# anemo5.net
KiCad netlist of a schematic drawn in EAGLE
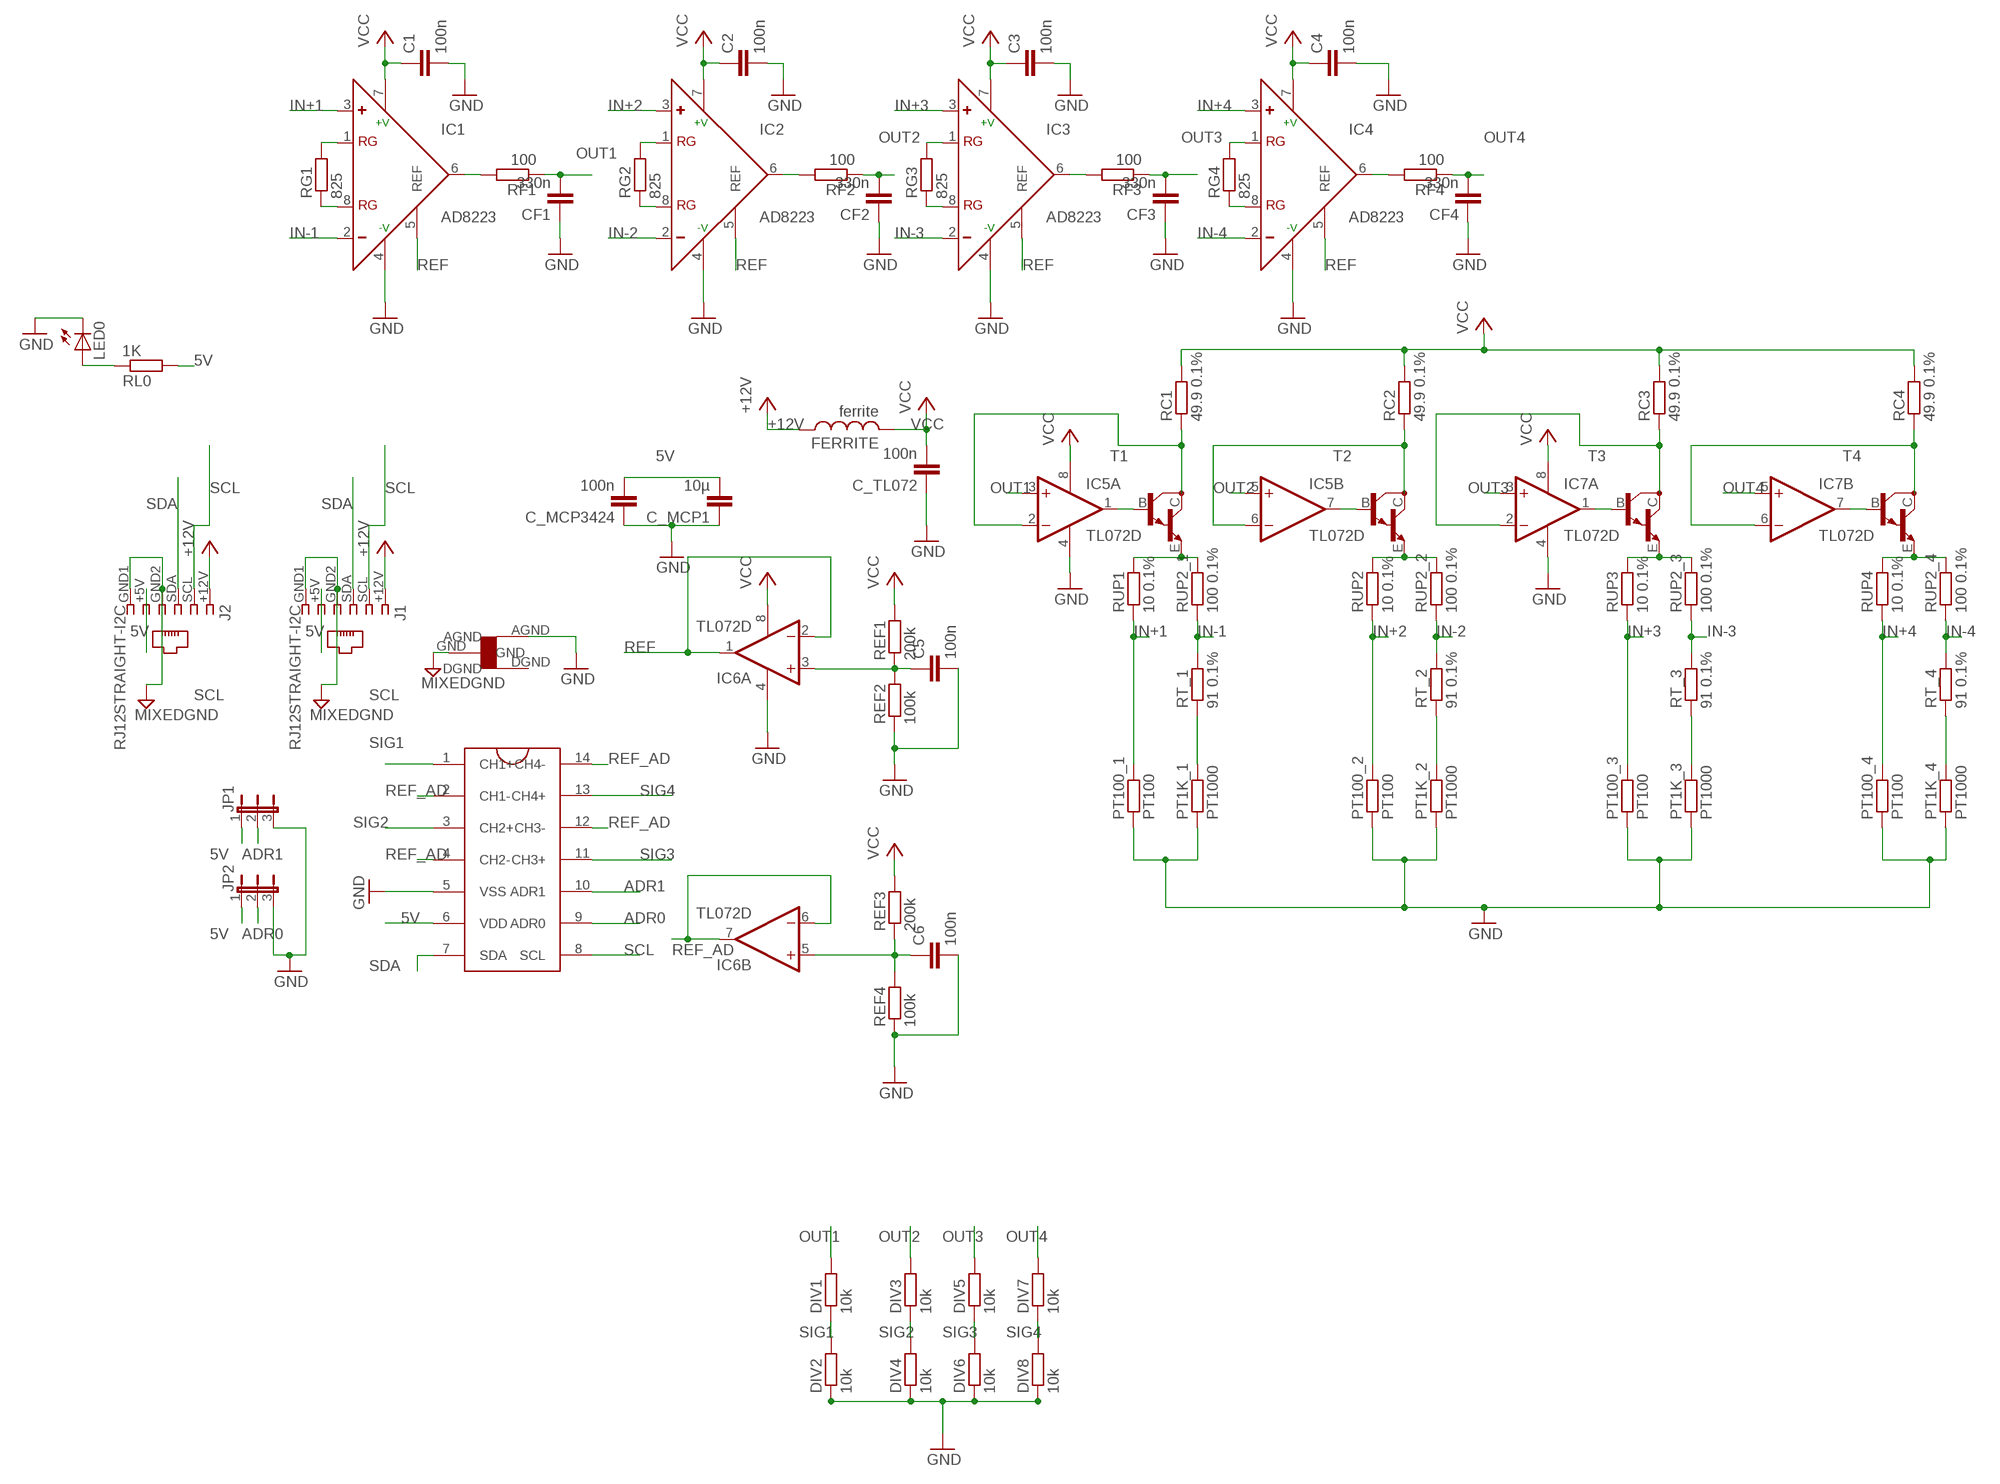
[diagram p0: schematic, sheet 1]

(export (version "E")
  (design (tool "Eeschema 10.0.6"))
  (components
    (comp (ref "C1")
      (value "100n")
      (footprint "eagle-import:C1206")
      (libsource (lib "eagle-import") (part "C-EUC1206"))
    )
    (comp (ref "C2")
      (value "100n")
      (footprint "eagle-import:C1206")
      (libsource (lib "eagle-import") (part "C-EUC1206"))
    )
    (comp (ref "C3")
      (value "100n")
      (footprint "eagle-import:C1206")
      (libsource (lib "eagle-import") (part "C-EUC1206"))
    )
    (comp (ref "C4")
      (value "100n")
      (footprint "eagle-import:C1206")
      (libsource (lib "eagle-import") (part "C-EUC1206"))
    )
    (comp (ref "C5")
      (value "100n")
      (footprint "eagle-import:C1206")
      (libsource (lib "eagle-import") (part "C-EUC1206"))
    )
    (comp (ref "C6")
      (value "100n")
      (footprint "eagle-import:C1206")
      (libsource (lib "eagle-import") (part "C-EUC1206"))
    )
    (comp (ref "CF1")
      (value "330n")
      (footprint "eagle-import:C1206")
      (libsource (lib "eagle-import") (part "C-EUC1206"))
    )
    (comp (ref "CF2")
      (value "330n")
      (footprint "eagle-import:C1206")
      (libsource (lib "eagle-import") (part "C-EUC1206"))
    )
    (comp (ref "CF3")
      (value "330n")
      (footprint "eagle-import:C1206")
      (libsource (lib "eagle-import") (part "C-EUC1206"))
    )
    (comp (ref "CF4")
      (value "330n")
      (footprint "eagle-import:C1206")
      (libsource (lib "eagle-import") (part "C-EUC1206"))
    )
    (comp (ref "C_MCP1")
      (value "10µ")
      (footprint "eagle-import:C1206")
      (libsource (lib "eagle-import") (part "C-EUC1206"))
    )
    (comp (ref "C_MCP3424")
      (value "100n")
      (footprint "eagle-import:C1206")
      (libsource (lib "eagle-import") (part "C-EUC1206"))
    )
    (comp (ref "C_TL072")
      (value "100n")
      (footprint "eagle-import:C1206")
      (libsource (lib "eagle-import") (part "C-EUC1206"))
    )
    (comp (ref "DIV1")
      (value "10k")
      (footprint "eagle-import:M1206")
      (libsource (lib "eagle-import") (part "R-EU_M1206"))
    )
    (comp (ref "DIV2")
      (value "10k")
      (footprint "eagle-import:M1206")
      (libsource (lib "eagle-import") (part "R-EU_M1206"))
    )
    (comp (ref "DIV3")
      (value "10k")
      (footprint "eagle-import:M1206")
      (libsource (lib "eagle-import") (part "R-EU_M1206"))
    )
    (comp (ref "DIV4")
      (value "10k")
      (footprint "eagle-import:M1206")
      (libsource (lib "eagle-import") (part "R-EU_M1206"))
    )
    (comp (ref "DIV5")
      (value "10k")
      (footprint "eagle-import:M1206")
      (libsource (lib "eagle-import") (part "R-EU_M1206"))
    )
    (comp (ref "DIV6")
      (value "10k")
      (footprint "eagle-import:M1206")
      (libsource (lib "eagle-import") (part "R-EU_M1206"))
    )
    (comp (ref "DIV7")
      (value "10k")
      (footprint "eagle-import:M1206")
      (libsource (lib "eagle-import") (part "R-EU_M1206"))
    )
    (comp (ref "DIV8")
      (value "10k")
      (footprint "eagle-import:M1206")
      (libsource (lib "eagle-import") (part "R-EU_M1206"))
    )
    (comp (ref "FERRITE")
      (value "ferrite")
      (footprint "eagle-import:L3216C")
      (libsource (lib "eagle-import") (part "L-USL3216C"))
    )
    (comp (ref "IC1")
      (value "AD8223")
      (footprint "eagle-import:SO8")
      (fields (field (name "MPN") "AD620AR"))
      (libsource (lib "eagle-import") (part "AD620R"))
    )
    (comp (ref "IC2")
      (value "AD8223")
      (footprint "eagle-import:SO8")
      (fields (field (name "MPN") "AD620AR"))
      (libsource (lib "eagle-import") (part "AD620R"))
    )
    (comp (ref "IC3")
      (value "AD8223")
      (footprint "eagle-import:SO8")
      (fields (field (name "MPN") "AD620AR"))
      (libsource (lib "eagle-import") (part "AD620R"))
    )
    (comp (ref "IC4")
      (value "AD8223")
      (footprint "eagle-import:SO8")
      (fields (field (name "MPN") "AD620AR"))
      (libsource (lib "eagle-import") (part "AD620R"))
    )
    (comp (ref "IC5")
      (value "TL072D")
      (footprint "eagle-import:SO08")
      (libsource (lib "eagle-import") (part "TL072D"))
    )
    (comp (ref "IC6")
      (value "TL072D")
      (footprint "eagle-import:SO08")
      (libsource (lib "eagle-import") (part "TL072D"))
    )
    (comp (ref "IC7")
      (value "TL072D")
      (footprint "eagle-import:SO08")
      (libsource (lib "eagle-import") (part "TL072D"))
    )
    (comp (ref "J1")
      (value "RJ12STRAIGHT-I2C")
      (footprint "eagle-import:RJ12-STRAIGHT-I2C")
      (libsource (lib "eagle-import") (part "RJ12STRAIGHT-I2C"))
    )
    (comp (ref "J2")
      (value "RJ12STRAIGHT-I2C")
      (footprint "eagle-import:RJ12-STRAIGHT-I2C")
      (libsource (lib "eagle-import") (part "RJ12STRAIGHT-I2C"))
    )
    (comp (ref "JP1")
      (value "JP2E")
      (footprint "eagle-import:JP2")
      (libsource (lib "eagle-import") (part "JP2E"))
    )
    (comp (ref "JP2")
      (value "JP2E")
      (footprint "eagle-import:JP2")
      (libsource (lib "eagle-import") (part "JP2E"))
    )
    (comp (ref "LED0")
      (value "LED1206")
      (footprint "eagle-import:LED-1206")
      (libsource (lib "eagle-import") (part "LED1206"))
    )
    (comp (ref "PT1K_1")
      (value "PT1000")
      (footprint "eagle-import:M1206")
      (libsource (lib "eagle-import") (part "R-EU_M1206"))
    )
    (comp (ref "PT1K_2")
      (value "PT1000")
      (footprint "eagle-import:M1206")
      (libsource (lib "eagle-import") (part "R-EU_M1206"))
    )
    (comp (ref "PT1K_3")
      (value "PT1000")
      (footprint "eagle-import:M1206")
      (libsource (lib "eagle-import") (part "R-EU_M1206"))
    )
    (comp (ref "PT1K_4")
      (value "PT1000")
      (footprint "eagle-import:M1206")
      (libsource (lib "eagle-import") (part "R-EU_M1206"))
    )
    (comp (ref "PT100_1")
      (value "PT100")
      (footprint "eagle-import:M1206")
      (libsource (lib "eagle-import") (part "R-EU_M1206"))
    )
    (comp (ref "PT100_2")
      (value "PT100")
      (footprint "eagle-import:M1206")
      (libsource (lib "eagle-import") (part "R-EU_M1206"))
    )
    (comp (ref "PT100_3")
      (value "PT100")
      (footprint "eagle-import:M1206")
      (libsource (lib "eagle-import") (part "R-EU_M1206"))
    )
    (comp (ref "PT100_4")
      (value "PT100")
      (footprint "eagle-import:M1206")
      (libsource (lib "eagle-import") (part "R-EU_M1206"))
    )
    (comp (ref "RC1")
      (value "49.9 0.1%")
      (footprint "eagle-import:M1206")
      (libsource (lib "eagle-import") (part "R-EU_M1206"))
    )
    (comp (ref "RC2")
      (value "49.9 0.1%")
      (footprint "eagle-import:M1206")
      (libsource (lib "eagle-import") (part "R-EU_M1206"))
    )
    (comp (ref "RC3")
      (value "49.9 0.1%")
      (footprint "eagle-import:M1206")
      (libsource (lib "eagle-import") (part "R-EU_M1206"))
    )
    (comp (ref "RC4")
      (value "49.9 0.1%")
      (footprint "eagle-import:M1206")
      (libsource (lib "eagle-import") (part "R-EU_M1206"))
    )
    (comp (ref "REF1")
      (value "200k")
      (footprint "eagle-import:M1206")
      (libsource (lib "eagle-import") (part "R-EU_M1206"))
    )
    (comp (ref "REF2")
      (value "100k")
      (footprint "eagle-import:M1206")
      (libsource (lib "eagle-import") (part "R-EU_M1206"))
    )
    (comp (ref "REF3")
      (value "200k")
      (footprint "eagle-import:M1206")
      (libsource (lib "eagle-import") (part "R-EU_M1206"))
    )
    (comp (ref "REF4")
      (value "100k")
      (footprint "eagle-import:M1206")
      (libsource (lib "eagle-import") (part "R-EU_M1206"))
    )
    (comp (ref "RF1")
      (value "100")
      (footprint "eagle-import:M1206")
      (libsource (lib "eagle-import") (part "R-EU_M1206"))
    )
    (comp (ref "RF2")
      (value "100")
      (footprint "eagle-import:M1206")
      (libsource (lib "eagle-import") (part "R-EU_M1206"))
    )
    (comp (ref "RF3")
      (value "100")
      (footprint "eagle-import:M1206")
      (libsource (lib "eagle-import") (part "R-EU_M1206"))
    )
    (comp (ref "RF4")
      (value "100")
      (footprint "eagle-import:M1206")
      (libsource (lib "eagle-import") (part "R-EU_M1206"))
    )
    (comp (ref "RG1")
      (value "825")
      (footprint "eagle-import:M1206")
      (libsource (lib "eagle-import") (part "R-EU_M1206"))
    )
    (comp (ref "RG2")
      (value "825")
      (footprint "eagle-import:M1206")
      (libsource (lib "eagle-import") (part "R-EU_M1206"))
    )
    (comp (ref "RG3")
      (value "825")
      (footprint "eagle-import:M1206")
      (libsource (lib "eagle-import") (part "R-EU_M1206"))
    )
    (comp (ref "RG4")
      (value "825")
      (footprint "eagle-import:M1206")
      (libsource (lib "eagle-import") (part "R-EU_M1206"))
    )
    (comp (ref "RL0")
      (value "1K")
      (footprint "eagle-import:M1206")
      (libsource (lib "eagle-import") (part "R-EU_M1206"))
    )
    (comp (ref "RT_1")
      (value "91 0.1%")
      (footprint "eagle-import:M1206")
      (libsource (lib "eagle-import") (part "R-EU_M1206"))
    )
    (comp (ref "RT_2")
      (value "91 0.1%")
      (footprint "eagle-import:M1206")
      (libsource (lib "eagle-import") (part "R-EU_M1206"))
    )
    (comp (ref "RT_3")
      (value "91 0.1%")
      (footprint "eagle-import:M1206")
      (libsource (lib "eagle-import") (part "R-EU_M1206"))
    )
    (comp (ref "RT_4")
      (value "91 0.1%")
      (footprint "eagle-import:M1206")
      (libsource (lib "eagle-import") (part "R-EU_M1206"))
    )
    (comp (ref "RUP1")
      (value "10 0.1%")
      (footprint "eagle-import:M1206")
      (libsource (lib "eagle-import") (part "R-EU_M1206"))
    )
    (comp (ref "RUP2")
      (value "10 0.1%")
      (footprint "eagle-import:M1206")
      (libsource (lib "eagle-import") (part "R-EU_M1206"))
    )
    (comp (ref "RUP2_1")
      (value "100 0.1%")
      (footprint "eagle-import:M1206")
      (libsource (lib "eagle-import") (part "R-EU_M1206"))
    )
    (comp (ref "RUP2_2")
      (value "100 0.1%")
      (footprint "eagle-import:M1206")
      (libsource (lib "eagle-import") (part "R-EU_M1206"))
    )
    (comp (ref "RUP2_3")
      (value "100 0.1%")
      (footprint "eagle-import:M1206")
      (libsource (lib "eagle-import") (part "R-EU_M1206"))
    )
    (comp (ref "RUP2_4")
      (value "100 0.1%")
      (footprint "eagle-import:M1206")
      (libsource (lib "eagle-import") (part "R-EU_M1206"))
    )
    (comp (ref "RUP3")
      (value "10 0.1%")
      (footprint "eagle-import:M1206")
      (libsource (lib "eagle-import") (part "R-EU_M1206"))
    )
    (comp (ref "RUP4")
      (value "10 0.1%")
      (footprint "eagle-import:M1206")
      (libsource (lib "eagle-import") (part "R-EU_M1206"))
    )
    (comp (ref "T1")
      (value "MMBTA13LT1-NPN_DARL-SOT23-BEC")
      (footprint "eagle-import:SOT23-BEC")
      (libsource (lib "eagle-import") (part "-NPN_DARL-SOT23-BECMMBTA13LT1"))
    )
    (comp (ref "T2")
      (value "MMBTA13LT1-NPN_DARL-SOT23-BEC")
      (footprint "eagle-import:SOT23-BEC")
      (libsource (lib "eagle-import") (part "-NPN_DARL-SOT23-BECMMBTA13LT1"))
    )
    (comp (ref "T3")
      (value "MMBTA13LT1-NPN_DARL-SOT23-BEC")
      (footprint "eagle-import:SOT23-BEC")
      (libsource (lib "eagle-import") (part "-NPN_DARL-SOT23-BECMMBTA13LT1"))
    )
    (comp (ref "T4")
      (value "MMBTA13LT1-NPN_DARL-SOT23-BEC")
      (footprint "eagle-import:SOT23-BEC")
      (libsource (lib "eagle-import") (part "-NPN_DARL-SOT23-BECMMBTA13LT1"))
    )
    (comp (ref "U$1")
      (value "MCP3424(SO14)")
      (footprint "eagle-import:14LDSOIC")
      (libsource (lib "eagle-import") (part "MCP3424(SO14)"))
    )
    (comp (ref "U$2")
      (value "STARGND")
      (footprint "eagle-import:STAR")
      (libsource (lib "eagle-import") (part "STARGND"))
    )
  )
  (nets
    (net (code "1") (name "+12V") (class "Default")
      (node (ref "FERRITE") (pin "1") (pinfunction "1_1") (pintype "passive"))
      (node (ref "J1") (pin "+12V") (pinfunction "1_+12V") (pintype "bidirectional"))
      (node (ref "J2") (pin "+12V") (pinfunction "1_+12V") (pintype "bidirectional"))
    )
    (net (code "2") (name "/5V") (class "Default")
      (node (ref "C_MCP1") (pin "2") (pinfunction "2_2") (pintype "passive"))
      (node (ref "C_MCP3424") (pin "2") (pinfunction "2_2") (pintype "passive"))
      (node (ref "J1") (pin "+5V") (pinfunction "5_+5V") (pintype "bidirectional"))
      (node (ref "J2") (pin "+5V") (pinfunction "5_+5V") (pintype "bidirectional"))
      (node (ref "JP1") (pin "1") (pinfunction "1_1") (pintype "passive"))
      (node (ref "JP2") (pin "1") (pinfunction "1_1") (pintype "passive"))
      (node (ref "RL0") (pin "2") (pinfunction "2_2") (pintype "passive"))
      (node (ref "U$1") (pin "6") (pinfunction "VDD_6") (pintype "bidirectional"))
    )
    (net (code "3") (name "/ADR0") (class "Default")
      (node (ref "JP2") (pin "2") (pinfunction "2_2") (pintype "passive"))
      (node (ref "U$1") (pin "9") (pinfunction "ADR0_9") (pintype "bidirectional"))
    )
    (net (code "4") (name "/ADR1") (class "Default")
      (node (ref "JP1") (pin "2") (pinfunction "2_2") (pintype "passive"))
      (node (ref "U$1") (pin "10") (pinfunction "ADR1_10") (pintype "bidirectional"))
    )
    (net (code "5") (name "/IN+1") (class "Default")
      (node (ref "IC1") (pin "3") (pinfunction "+_3") (pintype "input"))
      (node (ref "PT100_1") (pin "2") (pinfunction "2_2") (pintype "passive"))
      (node (ref "RUP1") (pin "1") (pinfunction "1_1") (pintype "passive"))
    )
    (net (code "6") (name "/IN+2") (class "Default")
      (node (ref "IC2") (pin "3") (pinfunction "+_3") (pintype "input"))
      (node (ref "PT100_2") (pin "2") (pinfunction "2_2") (pintype "passive"))
      (node (ref "RUP2") (pin "1") (pinfunction "1_1") (pintype "passive"))
    )
    (net (code "7") (name "/IN+3") (class "Default")
      (node (ref "IC3") (pin "3") (pinfunction "+_3") (pintype "input"))
      (node (ref "PT100_3") (pin "2") (pinfunction "2_2") (pintype "passive"))
      (node (ref "RUP3") (pin "1") (pinfunction "1_1") (pintype "passive"))
    )
    (net (code "8") (name "/IN+4") (class "Default")
      (node (ref "IC4") (pin "3") (pinfunction "+_3") (pintype "input"))
      (node (ref "PT100_4") (pin "2") (pinfunction "2_2") (pintype "passive"))
      (node (ref "RUP4") (pin "1") (pinfunction "1_1") (pintype "passive"))
    )
    (net (code "9") (name "/IN-1") (class "Default")
      (node (ref "IC1") (pin "2") (pinfunction "-_2") (pintype "input"))
      (node (ref "RT_1") (pin "2") (pinfunction "2_2") (pintype "passive"))
      (node (ref "RUP2_1") (pin "1") (pinfunction "1_1") (pintype "passive"))
    )
    (net (code "10") (name "/IN-2") (class "Default")
      (node (ref "IC2") (pin "2") (pinfunction "-_2") (pintype "input"))
      (node (ref "RT_2") (pin "2") (pinfunction "2_2") (pintype "passive"))
      (node (ref "RUP2_2") (pin "1") (pinfunction "1_1") (pintype "passive"))
    )
    (net (code "11") (name "/IN-3") (class "Default")
      (node (ref "IC3") (pin "2") (pinfunction "-_2") (pintype "input"))
      (node (ref "RT_3") (pin "2") (pinfunction "2_2") (pintype "passive"))
      (node (ref "RUP2_3") (pin "1") (pinfunction "1_1") (pintype "passive"))
    )
    (net (code "12") (name "/IN-4") (class "Default")
      (node (ref "IC4") (pin "2") (pinfunction "-_2") (pintype "input"))
      (node (ref "RT_4") (pin "2") (pinfunction "2_2") (pintype "passive"))
      (node (ref "RUP2_4") (pin "1") (pinfunction "1_1") (pintype "passive"))
    )
    (net (code "13") (name "/OUT1") (class "Default")
      (node (ref "CF1") (pin "2") (pinfunction "2_2") (pintype "passive"))
      (node (ref "DIV1") (pin "2") (pinfunction "2_2") (pintype "passive"))
      (node (ref "IC5") (pin "3") (pinfunction "+IN_3") (pintype "input"))
      (node (ref "RF1") (pin "1") (pinfunction "1_1") (pintype "passive"))
    )
    (net (code "14") (name "/OUT2") (class "Default")
      (node (ref "CF2") (pin "2") (pinfunction "2_2") (pintype "passive"))
      (node (ref "DIV3") (pin "2") (pinfunction "2_2") (pintype "passive"))
      (node (ref "IC5") (pin "5") (pinfunction "+IN_5") (pintype "input"))
      (node (ref "RF2") (pin "1") (pinfunction "1_1") (pintype "passive"))
    )
    (net (code "15") (name "/OUT3") (class "Default")
      (node (ref "CF3") (pin "2") (pinfunction "2_2") (pintype "passive"))
      (node (ref "DIV5") (pin "2") (pinfunction "2_2") (pintype "passive"))
      (node (ref "IC7") (pin "3") (pinfunction "+IN_3") (pintype "input"))
      (node (ref "RF3") (pin "1") (pinfunction "1_1") (pintype "passive"))
    )
    (net (code "16") (name "/OUT4") (class "Default")
      (node (ref "CF4") (pin "2") (pinfunction "2_2") (pintype "passive"))
      (node (ref "DIV7") (pin "2") (pinfunction "2_2") (pintype "passive"))
      (node (ref "IC7") (pin "5") (pinfunction "+IN_5") (pintype "input"))
      (node (ref "RF4") (pin "1") (pinfunction "1_1") (pintype "passive"))
    )
    (net (code "17") (name "/REF") (class "Default")
      (node (ref "IC1") (pin "5") (pinfunction "REF_5") (pintype "passive"))
      (node (ref "IC2") (pin "5") (pinfunction "REF_5") (pintype "passive"))
      (node (ref "IC3") (pin "5") (pinfunction "REF_5") (pintype "passive"))
      (node (ref "IC4") (pin "5") (pinfunction "REF_5") (pintype "passive"))
      (node (ref "IC6") (pin "1") (pinfunction "OUT_1") (pintype "output"))
      (node (ref "IC6") (pin "2") (pinfunction "-IN_2") (pintype "input"))
    )
    (net (code "18") (name "/REF_AD") (class "Default")
      (node (ref "IC6") (pin "6") (pinfunction "-IN_6") (pintype "input"))
      (node (ref "IC6") (pin "7") (pinfunction "OUT_7") (pintype "output"))
      (node (ref "U$1") (pin "12") (pinfunction "CH3-_12") (pintype "bidirectional"))
      (node (ref "U$1") (pin "14") (pinfunction "CH4-_14") (pintype "bidirectional"))
      (node (ref "U$1") (pin "2") (pinfunction "CH1-_2") (pintype "bidirectional"))
      (node (ref "U$1") (pin "4") (pinfunction "CH2-_4") (pintype "bidirectional"))
    )
    (net (code "19") (name "/SCL") (class "Default")
      (node (ref "J1") (pin "SCL") (pinfunction "2_SCL") (pintype "bidirectional"))
      (node (ref "J2") (pin "SCL") (pinfunction "2_SCL") (pintype "bidirectional"))
      (node (ref "U$1") (pin "8") (pinfunction "SCL_8") (pintype "bidirectional"))
    )
    (net (code "20") (name "/SDA") (class "Default")
      (node (ref "J1") (pin "SDA") (pinfunction "3_SDA") (pintype "bidirectional"))
      (node (ref "J2") (pin "SDA") (pinfunction "3_SDA") (pintype "bidirectional"))
      (node (ref "U$1") (pin "7") (pinfunction "SDA_7") (pintype "bidirectional"))
    )
    (net (code "21") (name "/SIG1") (class "Default")
      (node (ref "DIV1") (pin "1") (pinfunction "1_1") (pintype "passive"))
      (node (ref "DIV2") (pin "2") (pinfunction "2_2") (pintype "passive"))
      (node (ref "U$1") (pin "1") (pinfunction "CH1+_1") (pintype "bidirectional"))
    )
    (net (code "22") (name "/SIG2") (class "Default")
      (node (ref "DIV3") (pin "1") (pinfunction "1_1") (pintype "passive"))
      (node (ref "DIV4") (pin "2") (pinfunction "2_2") (pintype "passive"))
      (node (ref "U$1") (pin "3") (pinfunction "CH2+_3") (pintype "bidirectional"))
    )
    (net (code "23") (name "/SIG3") (class "Default")
      (node (ref "DIV5") (pin "1") (pinfunction "1_1") (pintype "passive"))
      (node (ref "DIV6") (pin "2") (pinfunction "2_2") (pintype "passive"))
      (node (ref "U$1") (pin "11") (pinfunction "CH3+_11") (pintype "bidirectional"))
    )
    (net (code "24") (name "/SIG4") (class "Default")
      (node (ref "DIV7") (pin "1") (pinfunction "1_1") (pintype "passive"))
      (node (ref "DIV8") (pin "2") (pinfunction "2_2") (pintype "passive"))
      (node (ref "U$1") (pin "13") (pinfunction "CH4+_13") (pintype "bidirectional"))
    )
    (net (code "25") (name "GND") (class "Default")
      (node (ref "C1") (pin "2") (pinfunction "2_2") (pintype "passive"))
      (node (ref "C2") (pin "2") (pinfunction "2_2") (pintype "passive"))
      (node (ref "C3") (pin "2") (pinfunction "2_2") (pintype "passive"))
      (node (ref "C4") (pin "2") (pinfunction "2_2") (pintype "passive"))
      (node (ref "C5") (pin "2") (pinfunction "2_2") (pintype "passive"))
      (node (ref "C6") (pin "2") (pinfunction "2_2") (pintype "passive"))
      (node (ref "CF1") (pin "1") (pinfunction "1_1") (pintype "passive"))
      (node (ref "CF2") (pin "1") (pinfunction "1_1") (pintype "passive"))
      (node (ref "CF3") (pin "1") (pinfunction "1_1") (pintype "passive"))
      (node (ref "CF4") (pin "1") (pinfunction "1_1") (pintype "passive"))
      (node (ref "C_MCP1") (pin "1") (pinfunction "1_1") (pintype "passive"))
      (node (ref "C_MCP3424") (pin "1") (pinfunction "1_1") (pintype "passive"))
      (node (ref "C_TL072") (pin "1") (pinfunction "1_1") (pintype "passive"))
      (node (ref "DIV2") (pin "1") (pinfunction "1_1") (pintype "passive"))
      (node (ref "DIV4") (pin "1") (pinfunction "1_1") (pintype "passive"))
      (node (ref "DIV6") (pin "1") (pinfunction "1_1") (pintype "passive"))
      (node (ref "DIV8") (pin "1") (pinfunction "1_1") (pintype "passive"))
      (node (ref "IC1") (pin "4") (pinfunction "-V_4") (pintype "power_in"))
      (node (ref "IC2") (pin "4") (pinfunction "-V_4") (pintype "power_in"))
      (node (ref "IC3") (pin "4") (pinfunction "-V_4") (pintype "power_in"))
      (node (ref "IC4") (pin "4") (pinfunction "-V_4") (pintype "power_in"))
      (node (ref "IC5") (pin "4") (pinfunction "V-_4") (pintype "power_in"))
      (node (ref "IC6") (pin "4") (pinfunction "V-_4") (pintype "power_in"))
      (node (ref "IC7") (pin "4") (pinfunction "V-_4") (pintype "power_in"))
      (node (ref "JP1") (pin "3") (pinfunction "3_3") (pintype "passive"))
      (node (ref "JP2") (pin "3") (pinfunction "3_3") (pintype "passive"))
      (node (ref "LED0") (pin "C") (pinfunction "C_C") (pintype "passive"))
      (node (ref "PT100_1") (pin "1") (pinfunction "1_1") (pintype "passive"))
      (node (ref "PT100_2") (pin "1") (pinfunction "1_1") (pintype "passive"))
      (node (ref "PT100_3") (pin "1") (pinfunction "1_1") (pintype "passive"))
      (node (ref "PT100_4") (pin "1") (pinfunction "1_1") (pintype "passive"))
      (node (ref "PT1K_1") (pin "1") (pinfunction "1_1") (pintype "passive"))
      (node (ref "PT1K_2") (pin "1") (pinfunction "1_1") (pintype "passive"))
      (node (ref "PT1K_3") (pin "1") (pinfunction "1_1") (pintype "passive"))
      (node (ref "PT1K_4") (pin "1") (pinfunction "1_1") (pintype "passive"))
      (node (ref "REF2") (pin "1") (pinfunction "1_1") (pintype "passive"))
      (node (ref "REF4") (pin "1") (pinfunction "1_1") (pintype "passive"))
      (node (ref "U$1") (pin "5") (pinfunction "VSS_5") (pintype "bidirectional"))
      (node (ref "U$2") (pin "AGND") (pinfunction "AGND_AGND") (pintype "output"))
    )
    (net (code "26") (name "MIXEDGND") (class "Default")
      (node (ref "J1") (pin "GND1") (pinfunction "6_GND1") (pintype "bidirectional"))
      (node (ref "J1") (pin "GND2") (pinfunction "4_GND2") (pintype "bidirectional"))
      (node (ref "J2") (pin "GND1") (pinfunction "6_GND1") (pintype "bidirectional"))
      (node (ref "J2") (pin "GND2") (pinfunction "4_GND2") (pintype "bidirectional"))
      (node (ref "U$2") (pin "GND") (pinfunction "GND_GND") (pintype "power_in"))
    )
    (net (code "27") (name "Net-(IC1-OUT)") (class "Default")
      (node (ref "IC1") (pin "6") (pinfunction "OUT_6") (pintype "output"))
      (node (ref "RF1") (pin "2") (pinfunction "2_2") (pintype "passive"))
    )
    (net (code "28") (name "Net-(IC1-RG-Pad1)") (class "Default")
      (node (ref "IC1") (pin "1") (pinfunction "RG_1") (pintype "passive"))
      (node (ref "RG1") (pin "2") (pinfunction "2_2") (pintype "passive"))
    )
    (net (code "29") (name "Net-(IC1-RG-Pad8)") (class "Default")
      (node (ref "IC1") (pin "8") (pinfunction "RG_8") (pintype "passive"))
      (node (ref "RG1") (pin "1") (pinfunction "1_1") (pintype "passive"))
    )
    (net (code "30") (name "Net-(IC2-OUT)") (class "Default")
      (node (ref "IC2") (pin "6") (pinfunction "OUT_6") (pintype "output"))
      (node (ref "RF2") (pin "2") (pinfunction "2_2") (pintype "passive"))
    )
    (net (code "31") (name "Net-(IC2-RG-Pad1)") (class "Default")
      (node (ref "IC2") (pin "1") (pinfunction "RG_1") (pintype "passive"))
      (node (ref "RG2") (pin "2") (pinfunction "2_2") (pintype "passive"))
    )
    (net (code "32") (name "Net-(IC2-RG-Pad8)") (class "Default")
      (node (ref "IC2") (pin "8") (pinfunction "RG_8") (pintype "passive"))
      (node (ref "RG2") (pin "1") (pinfunction "1_1") (pintype "passive"))
    )
    (net (code "33") (name "Net-(IC3-OUT)") (class "Default")
      (node (ref "IC3") (pin "6") (pinfunction "OUT_6") (pintype "output"))
      (node (ref "RF3") (pin "2") (pinfunction "2_2") (pintype "passive"))
    )
    (net (code "34") (name "Net-(IC3-RG-Pad1)") (class "Default")
      (node (ref "IC3") (pin "1") (pinfunction "RG_1") (pintype "passive"))
      (node (ref "RG3") (pin "2") (pinfunction "2_2") (pintype "passive"))
    )
    (net (code "35") (name "Net-(IC3-RG-Pad8)") (class "Default")
      (node (ref "IC3") (pin "8") (pinfunction "RG_8") (pintype "passive"))
      (node (ref "RG3") (pin "1") (pinfunction "1_1") (pintype "passive"))
    )
    (net (code "36") (name "Net-(IC4-OUT)") (class "Default")
      (node (ref "IC4") (pin "6") (pinfunction "OUT_6") (pintype "output"))
      (node (ref "RF4") (pin "2") (pinfunction "2_2") (pintype "passive"))
    )
    (net (code "37") (name "Net-(IC4-RG-Pad1)") (class "Default")
      (node (ref "IC4") (pin "1") (pinfunction "RG_1") (pintype "passive"))
      (node (ref "RG4") (pin "2") (pinfunction "2_2") (pintype "passive"))
    )
    (net (code "38") (name "Net-(IC4-RG-Pad8)") (class "Default")
      (node (ref "IC4") (pin "8") (pinfunction "RG_8") (pintype "passive"))
      (node (ref "RG4") (pin "1") (pinfunction "1_1") (pintype "passive"))
    )
    (net (code "39") (name "Net-(IC5A--IN)") (class "Default")
      (node (ref "IC5") (pin "2") (pinfunction "-IN_2") (pintype "input"))
      (node (ref "RC1") (pin "1") (pinfunction "1_1") (pintype "passive"))
      (node (ref "T1") (pin "C") (pinfunction "C_C") (pintype "passive"))
    )
    (net (code "40") (name "Net-(IC5A-OUT)") (class "Default")
      (node (ref "IC5") (pin "1") (pinfunction "OUT_1") (pintype "output"))
      (node (ref "T1") (pin "B") (pinfunction "B_B") (pintype "passive"))
    )
    (net (code "41") (name "Net-(IC5B--IN)") (class "Default")
      (node (ref "IC5") (pin "6") (pinfunction "-IN_6") (pintype "input"))
      (node (ref "RC2") (pin "1") (pinfunction "1_1") (pintype "passive"))
      (node (ref "T2") (pin "C") (pinfunction "C_C") (pintype "passive"))
    )
    (net (code "42") (name "Net-(IC5B-OUT)") (class "Default")
      (node (ref "IC5") (pin "7") (pinfunction "OUT_7") (pintype "output"))
      (node (ref "T2") (pin "B") (pinfunction "B_B") (pintype "passive"))
    )
    (net (code "43") (name "Net-(IC6A-+IN)") (class "Default")
      (node (ref "C5") (pin "1") (pinfunction "1_1") (pintype "passive"))
      (node (ref "IC6") (pin "3") (pinfunction "+IN_3") (pintype "input"))
      (node (ref "REF1") (pin "1") (pinfunction "1_1") (pintype "passive"))
      (node (ref "REF2") (pin "2") (pinfunction "2_2") (pintype "passive"))
    )
    (net (code "44") (name "Net-(IC6B-+IN)") (class "Default")
      (node (ref "C6") (pin "1") (pinfunction "1_1") (pintype "passive"))
      (node (ref "IC6") (pin "5") (pinfunction "+IN_5") (pintype "input"))
      (node (ref "REF3") (pin "1") (pinfunction "1_1") (pintype "passive"))
      (node (ref "REF4") (pin "2") (pinfunction "2_2") (pintype "passive"))
    )
    (net (code "45") (name "Net-(IC7A--IN)") (class "Default")
      (node (ref "IC7") (pin "2") (pinfunction "-IN_2") (pintype "input"))
      (node (ref "RC3") (pin "1") (pinfunction "1_1") (pintype "passive"))
      (node (ref "T3") (pin "C") (pinfunction "C_C") (pintype "passive"))
    )
    (net (code "46") (name "Net-(IC7A-OUT)") (class "Default")
      (node (ref "IC7") (pin "1") (pinfunction "OUT_1") (pintype "output"))
      (node (ref "T3") (pin "B") (pinfunction "B_B") (pintype "passive"))
    )
    (net (code "47") (name "Net-(IC7B--IN)") (class "Default")
      (node (ref "IC7") (pin "6") (pinfunction "-IN_6") (pintype "input"))
      (node (ref "RC4") (pin "1") (pinfunction "1_1") (pintype "passive"))
      (node (ref "T4") (pin "C") (pinfunction "C_C") (pintype "passive"))
    )
    (net (code "48") (name "Net-(IC7B-OUT)") (class "Default")
      (node (ref "IC7") (pin "7") (pinfunction "OUT_7") (pintype "output"))
      (node (ref "T4") (pin "B") (pinfunction "B_B") (pintype "passive"))
    )
    (net (code "49") (name "Net-(LED0-PadA)") (class "Default")
      (node (ref "LED0") (pin "A") (pinfunction "A_A") (pintype "passive"))
      (node (ref "RL0") (pin "1") (pinfunction "1_1") (pintype "passive"))
    )
    (net (code "50") (name "Net-(PT1K_1-Pad2)") (class "Default")
      (node (ref "PT1K_1") (pin "2") (pinfunction "2_2") (pintype "passive"))
      (node (ref "RT_1") (pin "1") (pinfunction "1_1") (pintype "passive"))
    )
    (net (code "51") (name "Net-(PT1K_2-Pad2)") (class "Default")
      (node (ref "PT1K_2") (pin "2") (pinfunction "2_2") (pintype "passive"))
      (node (ref "RT_2") (pin "1") (pinfunction "1_1") (pintype "passive"))
    )
    (net (code "52") (name "Net-(PT1K_3-Pad2)") (class "Default")
      (node (ref "PT1K_3") (pin "2") (pinfunction "2_2") (pintype "passive"))
      (node (ref "RT_3") (pin "1") (pinfunction "1_1") (pintype "passive"))
    )
    (net (code "53") (name "Net-(PT1K_4-Pad2)") (class "Default")
      (node (ref "PT1K_4") (pin "2") (pinfunction "2_2") (pintype "passive"))
      (node (ref "RT_4") (pin "1") (pinfunction "1_1") (pintype "passive"))
    )
    (net (code "54") (name "Net-(RUP1-Pad2)") (class "Default")
      (node (ref "RUP1") (pin "2") (pinfunction "2_2") (pintype "passive"))
      (node (ref "RUP2_1") (pin "2") (pinfunction "2_2") (pintype "passive"))
      (node (ref "T1") (pin "E") (pinfunction "E_E") (pintype "passive"))
    )
    (net (code "55") (name "Net-(RUP2-Pad2)") (class "Default")
      (node (ref "RUP2") (pin "2") (pinfunction "2_2") (pintype "passive"))
      (node (ref "RUP2_2") (pin "2") (pinfunction "2_2") (pintype "passive"))
      (node (ref "T2") (pin "E") (pinfunction "E_E") (pintype "passive"))
    )
    (net (code "56") (name "Net-(RUP2_3-Pad2)") (class "Default")
      (node (ref "RUP2_3") (pin "2") (pinfunction "2_2") (pintype "passive"))
      (node (ref "RUP3") (pin "2") (pinfunction "2_2") (pintype "passive"))
      (node (ref "T3") (pin "E") (pinfunction "E_E") (pintype "passive"))
    )
    (net (code "57") (name "Net-(RUP2_4-Pad2)") (class "Default")
      (node (ref "RUP2_4") (pin "2") (pinfunction "2_2") (pintype "passive"))
      (node (ref "RUP4") (pin "2") (pinfunction "2_2") (pintype "passive"))
      (node (ref "T4") (pin "E") (pinfunction "E_E") (pintype "passive"))
    )
    (net (code "58") (name "VCC") (class "Default")
      (node (ref "C1") (pin "1") (pinfunction "1_1") (pintype "passive"))
      (node (ref "C2") (pin "1") (pinfunction "1_1") (pintype "passive"))
      (node (ref "C3") (pin "1") (pinfunction "1_1") (pintype "passive"))
      (node (ref "C4") (pin "1") (pinfunction "1_1") (pintype "passive"))
      (node (ref "C_TL072") (pin "2") (pinfunction "2_2") (pintype "passive"))
      (node (ref "FERRITE") (pin "2") (pinfunction "2_2") (pintype "passive"))
      (node (ref "IC1") (pin "7") (pinfunction "+V_7") (pintype "power_in"))
      (node (ref "IC2") (pin "7") (pinfunction "+V_7") (pintype "power_in"))
      (node (ref "IC3") (pin "7") (pinfunction "+V_7") (pintype "power_in"))
      (node (ref "IC4") (pin "7") (pinfunction "+V_7") (pintype "power_in"))
      (node (ref "IC5") (pin "8") (pinfunction "V+_8") (pintype "power_in"))
      (node (ref "IC6") (pin "8") (pinfunction "V+_8") (pintype "power_in"))
      (node (ref "IC7") (pin "8") (pinfunction "V+_8") (pintype "power_in"))
      (node (ref "RC1") (pin "2") (pinfunction "2_2") (pintype "passive"))
      (node (ref "RC2") (pin "2") (pinfunction "2_2") (pintype "passive"))
      (node (ref "RC3") (pin "2") (pinfunction "2_2") (pintype "passive"))
      (node (ref "RC4") (pin "2") (pinfunction "2_2") (pintype "passive"))
      (node (ref "REF1") (pin "2") (pinfunction "2_2") (pintype "passive"))
      (node (ref "REF3") (pin "2") (pinfunction "2_2") (pintype "passive"))
    )
    (net (code "59") (name "unconnected-(U$2-PadDGND)") (class "Default")
      (node (ref "U$2") (pin "DGND") (pinfunction "DGND_DGND") (pintype "output"))
    )
  )
)
